# pinky_2_1.net
KiCad netlist of a schematic drawn in EAGLE
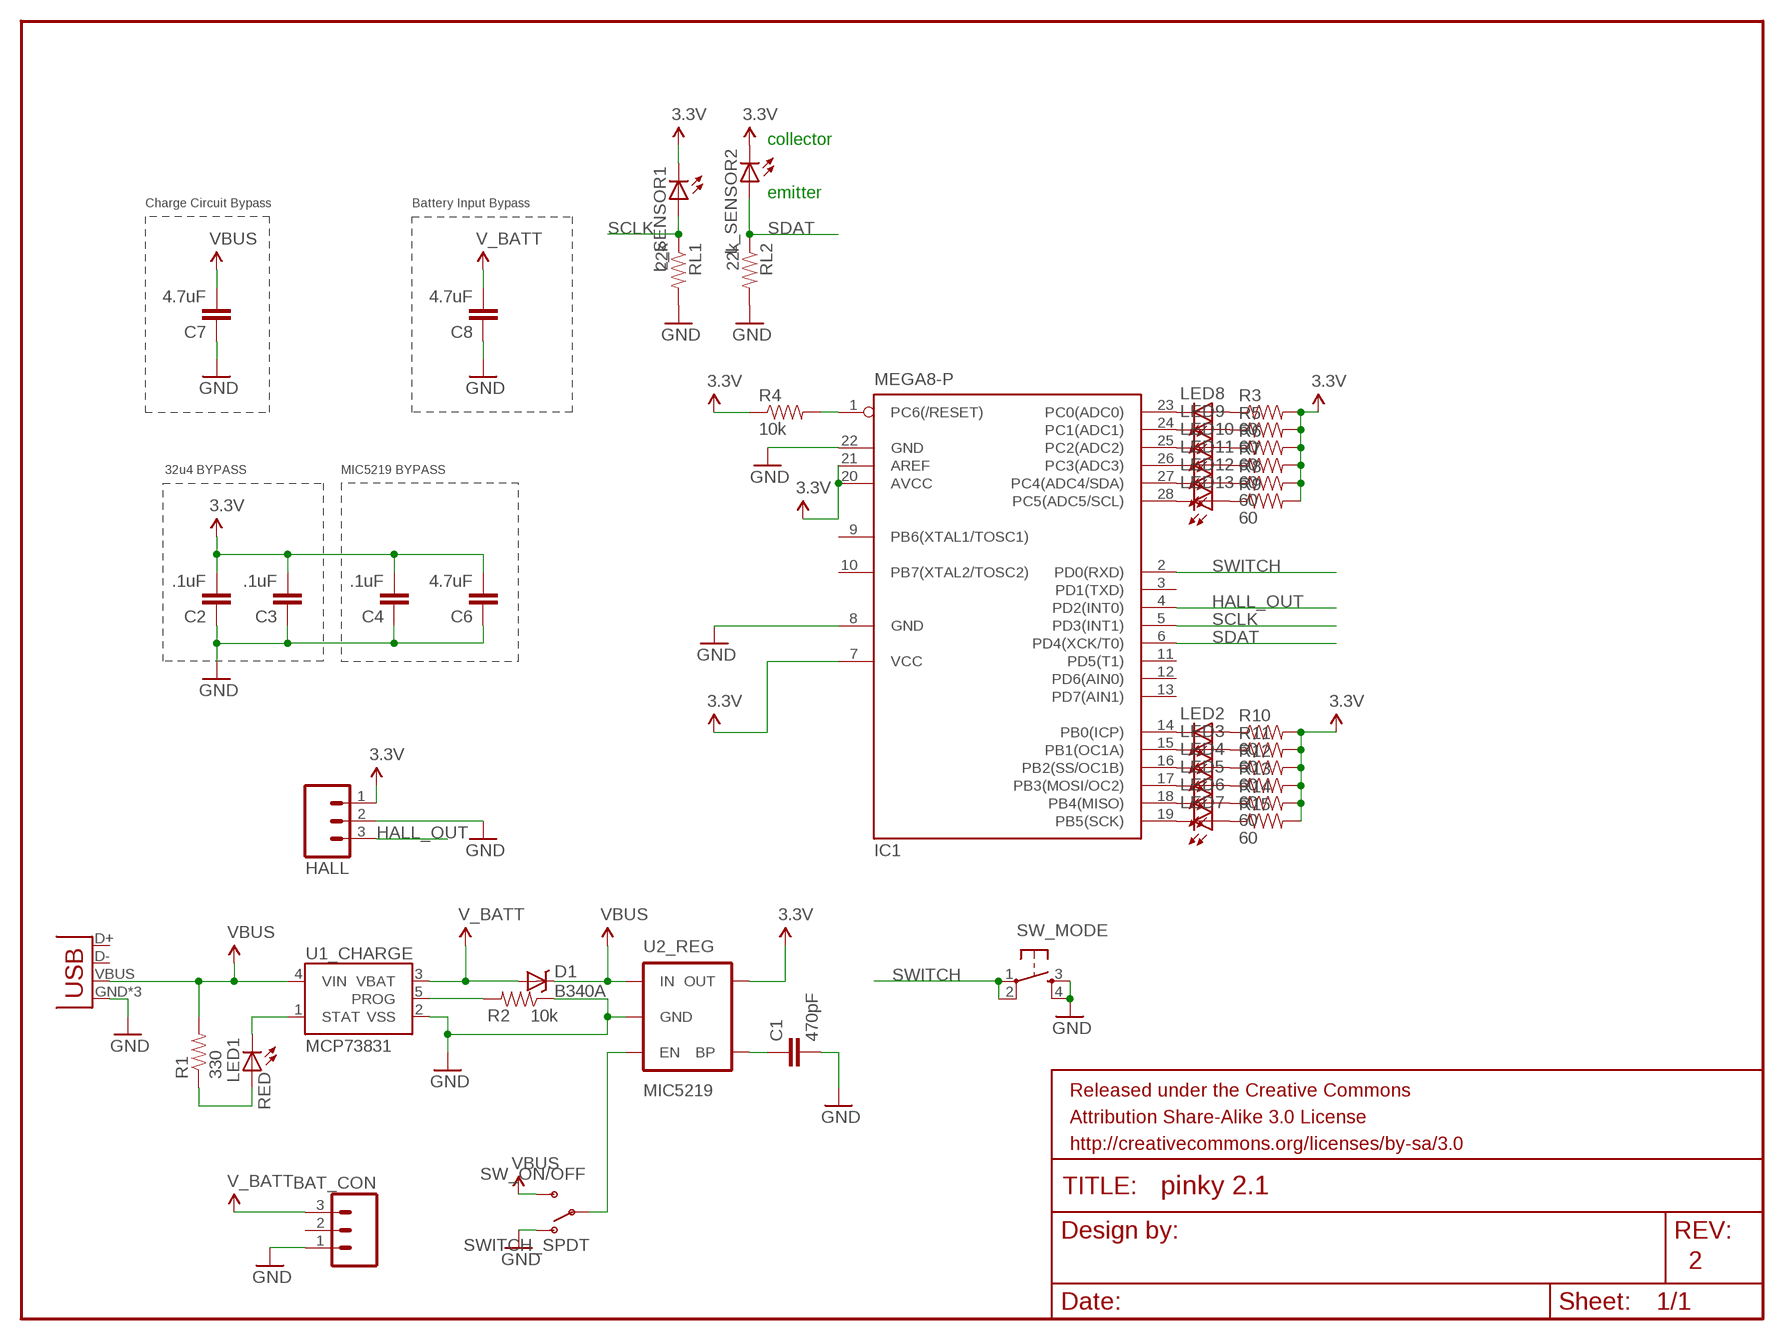
[diagram p0: schematic, sheet 1]

(export (version "E")
  (design (tool "Eeschema 10.0.6"))
  (components
    (comp (ref "BAT_CON")
      (value "M03PTH")
      (footprint "eagle-import:1X03")
      (libsource (lib "eagle-import") (part "M03PTH"))
    )
    (comp (ref "C1")
      (value "470pF")
      (footprint "eagle-import:1206")
      (libsource (lib "eagle-import") (part "CAP1206"))
    )
    (comp (ref "C2")
      (value ".1uF")
      (footprint "eagle-import:1206")
      (libsource (lib "eagle-import") (part "CAP1206"))
    )
    (comp (ref "C3")
      (value ".1uF")
      (footprint "eagle-import:1206")
      (libsource (lib "eagle-import") (part "CAP1206"))
    )
    (comp (ref "C4")
      (value ".1uF")
      (footprint "eagle-import:1206")
      (libsource (lib "eagle-import") (part "CAP1206"))
    )
    (comp (ref "C6")
      (value "4.7uF")
      (footprint "eagle-import:1206")
      (libsource (lib "eagle-import") (part "CAP1206"))
    )
    (comp (ref "C7")
      (value "4.7uF")
      (footprint "eagle-import:1206")
      (libsource (lib "eagle-import") (part "CAP1206"))
    )
    (comp (ref "C8")
      (value "4.7uF")
      (footprint "eagle-import:1206")
      (libsource (lib "eagle-import") (part "CAP1206"))
    )
    (comp (ref "D1")
      (value "B340A")
      (footprint "eagle-import:SMA-DIODE")
      (libsource (lib "eagle-import") (part "DIODE-SCHOTTKY_"))
    )
    (comp (ref "HALL")
      (value "M03PTH")
      (footprint "eagle-import:1X03")
      (libsource (lib "eagle-import") (part "M03PTH"))
    )
    (comp (ref "IC1")
      (value "MEGA8-P")
      (footprint "eagle-import:DIL28-3")
      (libsource (lib "eagle-import") (part "MEGA8-P"))
    )
    (comp (ref "LED1")
      (value "RED")
      (footprint "eagle-import:LED-1206")
      (libsource (lib "eagle-import") (part "LED1206"))
    )
    (comp (ref "LED2")
      (value "LED1206")
      (footprint "eagle-import:LED-1206")
      (libsource (lib "eagle-import") (part "LED1206"))
    )
    (comp (ref "LED3")
      (value "LED1206")
      (footprint "eagle-import:LED-1206")
      (libsource (lib "eagle-import") (part "LED1206"))
    )
    (comp (ref "LED4")
      (value "LED1206")
      (footprint "eagle-import:LED-1206")
      (libsource (lib "eagle-import") (part "LED1206"))
    )
    (comp (ref "LED5")
      (value "LED1206")
      (footprint "eagle-import:LED-1206")
      (libsource (lib "eagle-import") (part "LED1206"))
    )
    (comp (ref "LED6")
      (value "LED1206")
      (footprint "eagle-import:LED-1206")
      (libsource (lib "eagle-import") (part "LED1206"))
    )
    (comp (ref "LED7")
      (value "LED1206")
      (footprint "eagle-import:LED-1206")
      (libsource (lib "eagle-import") (part "LED1206"))
    )
    (comp (ref "LED8")
      (value "LED1206")
      (footprint "eagle-import:LED-1206")
      (libsource (lib "eagle-import") (part "LED1206"))
    )
    (comp (ref "LED9")
      (value "LED1206")
      (footprint "eagle-import:LED-1206")
      (libsource (lib "eagle-import") (part "LED1206"))
    )
    (comp (ref "LED10")
      (value "LED1206")
      (footprint "eagle-import:LED-1206")
      (libsource (lib "eagle-import") (part "LED1206"))
    )
    (comp (ref "LED11")
      (value "LED1206")
      (footprint "eagle-import:LED-1206")
      (libsource (lib "eagle-import") (part "LED1206"))
    )
    (comp (ref "LED12")
      (value "LED1206")
      (footprint "eagle-import:LED-1206")
      (libsource (lib "eagle-import") (part "LED1206"))
    )
    (comp (ref "LED13")
      (value "LED1206")
      (footprint "eagle-import:LED-1206")
      (libsource (lib "eagle-import") (part "LED1206"))
    )
    (comp (ref "L_SENSOR1")
      (value "LED3MM")
      (footprint "eagle-import:LED3MM")
      (libsource (lib "eagle-import") (part "LED3MM"))
    )
    (comp (ref "L_SENSOR2")
      (value "LED3MM")
      (footprint "eagle-import:LED3MM")
      (libsource (lib "eagle-import") (part "LED3MM"))
    )
    (comp (ref "R1")
      (value "330")
      (footprint "eagle-import:1206")
      (libsource (lib "eagle-import") (part "RESISTOR1206"))
    )
    (comp (ref "R2")
      (value "10k")
      (footprint "eagle-import:1206")
      (libsource (lib "eagle-import") (part "RESISTOR1206"))
    )
    (comp (ref "R3")
      (value "60")
      (footprint "eagle-import:1206")
      (libsource (lib "eagle-import") (part "RESISTOR1206"))
    )
    (comp (ref "R4")
      (value "10k")
      (footprint "eagle-import:1206")
      (libsource (lib "eagle-import") (part "RESISTOR1206"))
    )
    (comp (ref "R5")
      (value "60")
      (footprint "eagle-import:1206")
      (libsource (lib "eagle-import") (part "RESISTOR1206"))
    )
    (comp (ref "R6")
      (value "60")
      (footprint "eagle-import:1206")
      (libsource (lib "eagle-import") (part "RESISTOR1206"))
    )
    (comp (ref "R7")
      (value "60")
      (footprint "eagle-import:1206")
      (libsource (lib "eagle-import") (part "RESISTOR1206"))
    )
    (comp (ref "R8")
      (value "60")
      (footprint "eagle-import:1206")
      (libsource (lib "eagle-import") (part "RESISTOR1206"))
    )
    (comp (ref "R9")
      (value "60")
      (footprint "eagle-import:1206")
      (libsource (lib "eagle-import") (part "RESISTOR1206"))
    )
    (comp (ref "R10")
      (value "60")
      (footprint "eagle-import:1206")
      (libsource (lib "eagle-import") (part "RESISTOR1206"))
    )
    (comp (ref "R11")
      (value "60")
      (footprint "eagle-import:1206")
      (libsource (lib "eagle-import") (part "RESISTOR1206"))
    )
    (comp (ref "R12")
      (value "60")
      (footprint "eagle-import:1206")
      (libsource (lib "eagle-import") (part "RESISTOR1206"))
    )
    (comp (ref "R13")
      (value "60")
      (footprint "eagle-import:1206")
      (libsource (lib "eagle-import") (part "RESISTOR1206"))
    )
    (comp (ref "R14")
      (value "60")
      (footprint "eagle-import:1206")
      (libsource (lib "eagle-import") (part "RESISTOR1206"))
    )
    (comp (ref "R15")
      (value "60")
      (footprint "eagle-import:1206")
      (libsource (lib "eagle-import") (part "RESISTOR1206"))
    )
    (comp (ref "RL1")
      (value "22k")
      (footprint "eagle-import:1206")
      (libsource (lib "eagle-import") (part "RESISTOR1206"))
    )
    (comp (ref "RL2")
      (value "22k")
      (footprint "eagle-import:1206")
      (libsource (lib "eagle-import") (part "RESISTOR1206"))
    )
    (comp (ref "SW_MODE")
      (value "TAC_SWITCHPTH")
      (footprint "eagle-import:TACTILE-PTH")
      (libsource (lib "eagle-import") (part "TAC_SWITCHPTH"))
    )
    (comp (ref "SW_ON/OFF")
      (value "SWITCH_SPDT")
      (footprint "eagle-import:KPS-1290")
      (libsource (lib "eagle-import") (part "SWITCH_SPDT"))
    )
    (comp (ref "U1_CHARGE")
      (value "MCP73831")
      (footprint "eagle-import:SOT23-5")
      (libsource (lib "eagle-import") (part "MCP73831"))
    )
    (comp (ref "U2_REG")
      (value "MIC5219")
      (footprint "eagle-import:SOT23-5")
      (libsource (lib "eagle-import") (part "V_REG_MIC5219SMD"))
    )
    (comp (ref "X1_USB_MICRO")
      (value "USB-MICROB")
      (footprint "eagle-import:USB-MICROB")
      (libsource (lib "eagle-import") (part "USB-MICROB"))
    )
  )
  (nets
    (net (code "1") (name "/HALL_OUT") (class "Default")
      (node (ref "HALL") (pin "3") (pinfunction "3_3") (pintype "passive"))
      (node (ref "IC1") (pin "4") (pinfunction "PD2(INT0)_4") (pintype "bidirectional"))
    )
    (net (code "2") (name "/SCLK") (class "Default")
      (node (ref "IC1") (pin "5") (pinfunction "PD3(INT1)_5") (pintype "bidirectional"))
      (node (ref "L_SENSOR1") (pin "A") (pinfunction "A_A") (pintype "passive"))
      (node (ref "RL1") (pin "1") (pinfunction "1_1") (pintype "passive"))
    )
    (net (code "3") (name "/SDAT") (class "Default")
      (node (ref "IC1") (pin "6") (pinfunction "PD4(XCK/T0)_6") (pintype "bidirectional"))
      (node (ref "L_SENSOR2") (pin "A") (pinfunction "A_A") (pintype "passive"))
      (node (ref "RL2") (pin "1") (pinfunction "1_1") (pintype "passive"))
    )
    (net (code "4") (name "/SWITCH") (class "Default")
      (node (ref "IC1") (pin "2") (pinfunction "PD0(RXD)_2") (pintype "bidirectional"))
      (node (ref "SW_MODE") (pin "1") (pinfunction "1_1") (pintype "passive"))
      (node (ref "SW_MODE") (pin "2") (pinfunction "2_2") (pintype "passive"))
    )
    (net (code "5") (name "3.3V") (class "Default")
      (node (ref "C2") (pin "2") (pinfunction "2_2") (pintype "passive"))
      (node (ref "C3") (pin "2") (pinfunction "2_2") (pintype "passive"))
      (node (ref "C4") (pin "2") (pinfunction "2_2") (pintype "passive"))
      (node (ref "C6") (pin "2") (pinfunction "2_2") (pintype "passive"))
      (node (ref "HALL") (pin "1") (pinfunction "1_1") (pintype "passive"))
      (node (ref "IC1") (pin "20") (pinfunction "AVCC_20") (pintype "power_in"))
      (node (ref "IC1") (pin "21") (pinfunction "AREF_21") (pintype "passive"))
      (node (ref "IC1") (pin "7") (pinfunction "VCC_7") (pintype "power_in"))
      (node (ref "L_SENSOR1") (pin "K") (pinfunction "C_K") (pintype "passive"))
      (node (ref "L_SENSOR2") (pin "K") (pinfunction "C_K") (pintype "passive"))
      (node (ref "R10") (pin "2") (pinfunction "2_2") (pintype "passive"))
      (node (ref "R11") (pin "2") (pinfunction "2_2") (pintype "passive"))
      (node (ref "R12") (pin "2") (pinfunction "2_2") (pintype "passive"))
      (node (ref "R13") (pin "2") (pinfunction "2_2") (pintype "passive"))
      (node (ref "R14") (pin "2") (pinfunction "2_2") (pintype "passive"))
      (node (ref "R15") (pin "2") (pinfunction "2_2") (pintype "passive"))
      (node (ref "R3") (pin "2") (pinfunction "2_2") (pintype "passive"))
      (node (ref "R4") (pin "1") (pinfunction "1_1") (pintype "passive"))
      (node (ref "R5") (pin "2") (pinfunction "2_2") (pintype "passive"))
      (node (ref "R6") (pin "2") (pinfunction "2_2") (pintype "passive"))
      (node (ref "R7") (pin "2") (pinfunction "2_2") (pintype "passive"))
      (node (ref "R8") (pin "2") (pinfunction "2_2") (pintype "passive"))
      (node (ref "R9") (pin "2") (pinfunction "2_2") (pintype "passive"))
      (node (ref "U2_REG") (pin "5") (pinfunction "OUT_5") (pintype "passive"))
    )
    (net (code "6") (name "GND") (class "Default")
      (node (ref "BAT_CON") (pin "1") (pinfunction "1_1") (pintype "passive"))
      (node (ref "C1") (pin "2") (pinfunction "2_2") (pintype "passive"))
      (node (ref "C2") (pin "1") (pinfunction "1_1") (pintype "passive"))
      (node (ref "C3") (pin "1") (pinfunction "1_1") (pintype "passive"))
      (node (ref "C4") (pin "1") (pinfunction "1_1") (pintype "passive"))
      (node (ref "C6") (pin "1") (pinfunction "1_1") (pintype "passive"))
      (node (ref "C7") (pin "1") (pinfunction "1_1") (pintype "passive"))
      (node (ref "C8") (pin "1") (pinfunction "1_1") (pintype "passive"))
      (node (ref "HALL") (pin "2") (pinfunction "2_2") (pintype "passive"))
      (node (ref "IC1") (pin "22") (pinfunction "GND_22") (pintype "power_in"))
      (node (ref "IC1") (pin "8") (pinfunction "GND_8") (pintype "power_in"))
      (node (ref "R2") (pin "1") (pinfunction "1_1") (pintype "passive"))
      (node (ref "RL1") (pin "2") (pinfunction "2_2") (pintype "passive"))
      (node (ref "RL2") (pin "2") (pinfunction "2_2") (pintype "passive"))
      (node (ref "SW_MODE") (pin "3") (pinfunction "3_3") (pintype "passive"))
      (node (ref "SW_MODE") (pin "4") (pinfunction "4_4") (pintype "passive"))
      (node (ref "SW_ON/OFF") (pin "O") (pinfunction "O_O") (pintype "passive"))
      (node (ref "U1_CHARGE") (pin "2") (pinfunction "VSS_2") (pintype "power_in"))
      (node (ref "U2_REG") (pin "2") (pinfunction "GND_2") (pintype "input"))
      (node (ref "X1_USB_MICRO") (pin "GND") (pinfunction "GND_GND") (pintype "bidirectional"))
      (node (ref "X1_USB_MICRO") (pin "MT1") (pinfunction "GND_MT1") (pintype "bidirectional"))
      (node (ref "X1_USB_MICRO") (pin "MT2") (pinfunction "GND_MT2") (pintype "bidirectional"))
    )
    (net (code "7") (name "Net-(IC1-PB0(ICP))") (class "Default")
      (node (ref "IC1") (pin "14") (pinfunction "PB0(ICP)_14") (pintype "bidirectional"))
      (node (ref "LED2") (pin "C") (pinfunction "C_C") (pintype "passive"))
    )
    (net (code "8") (name "Net-(IC1-PB1(OC1A))") (class "Default")
      (node (ref "IC1") (pin "15") (pinfunction "PB1(OC1A)_15") (pintype "bidirectional"))
      (node (ref "LED3") (pin "C") (pinfunction "C_C") (pintype "passive"))
    )
    (net (code "9") (name "Net-(IC1-PB2(SS{slash}OC1B))") (class "Default")
      (node (ref "IC1") (pin "16") (pinfunction "PB2(SS/OC1B)_16") (pintype "bidirectional"))
      (node (ref "LED4") (pin "C") (pinfunction "C_C") (pintype "passive"))
    )
    (net (code "10") (name "Net-(IC1-PB3(MOSI{slash}OC2))") (class "Default")
      (node (ref "IC1") (pin "17") (pinfunction "PB3(MOSI/OC2)_17") (pintype "bidirectional"))
      (node (ref "LED5") (pin "C") (pinfunction "C_C") (pintype "passive"))
    )
    (net (code "11") (name "Net-(IC1-PB4(MISO))") (class "Default")
      (node (ref "IC1") (pin "18") (pinfunction "PB4(MISO)_18") (pintype "bidirectional"))
      (node (ref "LED6") (pin "C") (pinfunction "C_C") (pintype "passive"))
    )
    (net (code "12") (name "Net-(IC1-PB5(SCK))") (class "Default")
      (node (ref "IC1") (pin "19") (pinfunction "PB5(SCK)_19") (pintype "bidirectional"))
      (node (ref "LED7") (pin "C") (pinfunction "C_C") (pintype "passive"))
    )
    (net (code "13") (name "Net-(IC1-PC0(ADC0))") (class "Default")
      (node (ref "IC1") (pin "23") (pinfunction "PC0(ADC0)_23") (pintype "bidirectional"))
      (node (ref "LED8") (pin "C") (pinfunction "C_C") (pintype "passive"))
    )
    (net (code "14") (name "Net-(IC1-PC1(ADC1))") (class "Default")
      (node (ref "IC1") (pin "24") (pinfunction "PC1(ADC1)_24") (pintype "bidirectional"))
      (node (ref "LED9") (pin "C") (pinfunction "C_C") (pintype "passive"))
    )
    (net (code "15") (name "Net-(IC1-PC2(ADC2))") (class "Default")
      (node (ref "IC1") (pin "25") (pinfunction "PC2(ADC2)_25") (pintype "bidirectional"))
      (node (ref "LED10") (pin "C") (pinfunction "C_C") (pintype "passive"))
    )
    (net (code "16") (name "Net-(IC1-PC3(ADC3))") (class "Default")
      (node (ref "IC1") (pin "26") (pinfunction "PC3(ADC3)_26") (pintype "bidirectional"))
      (node (ref "LED11") (pin "C") (pinfunction "C_C") (pintype "passive"))
    )
    (net (code "17") (name "Net-(IC1-PC4(ADC4{slash}SDA))") (class "Default")
      (node (ref "IC1") (pin "27") (pinfunction "PC4(ADC4/SDA)_27") (pintype "bidirectional"))
      (node (ref "LED12") (pin "C") (pinfunction "C_C") (pintype "passive"))
    )
    (net (code "18") (name "Net-(IC1-PC5(ADC5{slash}SCL))") (class "Default")
      (node (ref "IC1") (pin "28") (pinfunction "PC5(ADC5/SCL)_28") (pintype "bidirectional"))
      (node (ref "LED13") (pin "C") (pinfunction "C_C") (pintype "passive"))
    )
    (net (code "19") (name "Net-(IC1-PC6({slash}RESET))") (class "Default")
      (node (ref "IC1") (pin "1") (pinfunction "PC6(/RESET)_1") (pintype "bidirectional"))
      (node (ref "R4") (pin "2") (pinfunction "2_2") (pintype "passive"))
    )
    (net (code "20") (name "Net-(LED1-PadA)") (class "Default")
      (node (ref "LED1") (pin "A") (pinfunction "A_A") (pintype "passive"))
      (node (ref "R1") (pin "1") (pinfunction "1_1") (pintype "passive"))
    )
    (net (code "21") (name "Net-(LED2-PadA)") (class "Default")
      (node (ref "LED2") (pin "A") (pinfunction "A_A") (pintype "passive"))
      (node (ref "R10") (pin "1") (pinfunction "1_1") (pintype "passive"))
    )
    (net (code "22") (name "Net-(LED3-PadA)") (class "Default")
      (node (ref "LED3") (pin "A") (pinfunction "A_A") (pintype "passive"))
      (node (ref "R11") (pin "1") (pinfunction "1_1") (pintype "passive"))
    )
    (net (code "23") (name "Net-(LED4-PadA)") (class "Default")
      (node (ref "LED4") (pin "A") (pinfunction "A_A") (pintype "passive"))
      (node (ref "R12") (pin "1") (pinfunction "1_1") (pintype "passive"))
    )
    (net (code "24") (name "Net-(LED5-PadA)") (class "Default")
      (node (ref "LED5") (pin "A") (pinfunction "A_A") (pintype "passive"))
      (node (ref "R13") (pin "1") (pinfunction "1_1") (pintype "passive"))
    )
    (net (code "25") (name "Net-(LED6-PadA)") (class "Default")
      (node (ref "LED6") (pin "A") (pinfunction "A_A") (pintype "passive"))
      (node (ref "R14") (pin "1") (pinfunction "1_1") (pintype "passive"))
    )
    (net (code "26") (name "Net-(LED7-PadA)") (class "Default")
      (node (ref "LED7") (pin "A") (pinfunction "A_A") (pintype "passive"))
      (node (ref "R15") (pin "1") (pinfunction "1_1") (pintype "passive"))
    )
    (net (code "27") (name "Net-(LED8-PadA)") (class "Default")
      (node (ref "LED8") (pin "A") (pinfunction "A_A") (pintype "passive"))
      (node (ref "R3") (pin "1") (pinfunction "1_1") (pintype "passive"))
    )
    (net (code "28") (name "Net-(LED9-PadA)") (class "Default")
      (node (ref "LED9") (pin "A") (pinfunction "A_A") (pintype "passive"))
      (node (ref "R5") (pin "1") (pinfunction "1_1") (pintype "passive"))
    )
    (net (code "29") (name "Net-(LED10-PadA)") (class "Default")
      (node (ref "LED10") (pin "A") (pinfunction "A_A") (pintype "passive"))
      (node (ref "R6") (pin "1") (pinfunction "1_1") (pintype "passive"))
    )
    (net (code "30") (name "Net-(LED11-PadA)") (class "Default")
      (node (ref "LED11") (pin "A") (pinfunction "A_A") (pintype "passive"))
      (node (ref "R7") (pin "1") (pinfunction "1_1") (pintype "passive"))
    )
    (net (code "31") (name "Net-(LED12-PadA)") (class "Default")
      (node (ref "LED12") (pin "A") (pinfunction "A_A") (pintype "passive"))
      (node (ref "R8") (pin "1") (pinfunction "1_1") (pintype "passive"))
    )
    (net (code "32") (name "Net-(LED13-PadA)") (class "Default")
      (node (ref "LED13") (pin "A") (pinfunction "A_A") (pintype "passive"))
      (node (ref "R9") (pin "1") (pinfunction "1_1") (pintype "passive"))
    )
    (net (code "33") (name "Net-(U1_CHARGE-PROG)") (class "Default")
      (node (ref "R2") (pin "2") (pinfunction "2_2") (pintype "passive"))
      (node (ref "U1_CHARGE") (pin "5") (pinfunction "PROG_5") (pintype "input"))
    )
    (net (code "34") (name "Net-(U1_CHARGE-STAT)") (class "Default")
      (node (ref "LED1") (pin "C") (pinfunction "C_C") (pintype "passive"))
      (node (ref "U1_CHARGE") (pin "1") (pinfunction "STAT_1") (pintype "output"))
    )
    (net (code "35") (name "Net-(U2_REG-BP)") (class "Default")
      (node (ref "C1") (pin "1") (pinfunction "1_1") (pintype "passive"))
      (node (ref "U2_REG") (pin "4") (pinfunction "BP_4") (pintype "input"))
    )
    (net (code "36") (name "Net-(U2_REG-EN)") (class "Default")
      (node (ref "SW_ON/OFF") (pin "P") (pinfunction "P_P") (pintype "passive"))
      (node (ref "U2_REG") (pin "3") (pinfunction "EN_3") (pintype "input"))
    )
    (net (code "37") (name "VBUS") (class "Default")
      (node (ref "C7") (pin "2") (pinfunction "2_2") (pintype "passive"))
      (node (ref "D1") (pin "C") (pinfunction "C_C") (pintype "passive"))
      (node (ref "R1") (pin "2") (pinfunction "2_2") (pintype "passive"))
      (node (ref "SW_ON/OFF") (pin "S") (pinfunction "S_S") (pintype "passive"))
      (node (ref "U1_CHARGE") (pin "4") (pinfunction "VIN_4") (pintype "power_in"))
      (node (ref "U2_REG") (pin "1") (pinfunction "IN_1") (pintype "input"))
      (node (ref "X1_USB_MICRO") (pin "VBUS") (pinfunction "VBUS_VBUS") (pintype "bidirectional"))
    )
    (net (code "38") (name "V_BATT") (class "Default")
      (node (ref "BAT_CON") (pin "3") (pinfunction "3_3") (pintype "passive"))
      (node (ref "C8") (pin "2") (pinfunction "2_2") (pintype "passive"))
      (node (ref "D1") (pin "A") (pinfunction "A_A") (pintype "passive"))
      (node (ref "U1_CHARGE") (pin "3") (pinfunction "VBAT_3") (pintype "power_in"))
    )
    (net (code "39") (name "unconnected-(BAT_CON-Pad2)") (class "Default")
      (node (ref "BAT_CON") (pin "2") (pinfunction "2_2") (pintype "passive"))
    )
    (net (code "40") (name "unconnected-(IC1-PB6(XTAL1{slash}TOSC1)-Pad9)") (class "Default")
      (node (ref "IC1") (pin "9") (pinfunction "PB6(XTAL1/TOSC1)_9") (pintype "bidirectional"))
    )
    (net (code "41") (name "unconnected-(IC1-PB7(XTAL2{slash}TOSC2)-Pad10)") (class "Default")
      (node (ref "IC1") (pin "10") (pinfunction "PB7(XTAL2/TOSC2)_10") (pintype "bidirectional"))
    )
    (net (code "42") (name "unconnected-(IC1-PD1(TXD)-Pad3)") (class "Default")
      (node (ref "IC1") (pin "3") (pinfunction "PD1(TXD)_3") (pintype "bidirectional"))
    )
    (net (code "43") (name "unconnected-(IC1-PD5(T1)-Pad11)") (class "Default")
      (node (ref "IC1") (pin "11") (pinfunction "PD5(T1)_11") (pintype "bidirectional"))
    )
    (net (code "44") (name "unconnected-(IC1-PD6(AIN0)-Pad12)") (class "Default")
      (node (ref "IC1") (pin "12") (pinfunction "PD6(AIN0)_12") (pintype "bidirectional"))
    )
    (net (code "45") (name "unconnected-(IC1-PD7(AIN1)-Pad13)") (class "Default")
      (node (ref "IC1") (pin "13") (pinfunction "PD7(AIN1)_13") (pintype "bidirectional"))
    )
    (net (code "46") (name "unconnected-(X1_USB_MICRO-PadD+)") (class "Default")
      (node (ref "X1_USB_MICRO") (pin "D+") (pinfunction "D+_D+") (pintype "bidirectional"))
    )
    (net (code "47") (name "unconnected-(X1_USB_MICRO-PadD-)") (class "Default")
      (node (ref "X1_USB_MICRO") (pin "D-") (pinfunction "D-_D-") (pintype "bidirectional"))
    )
  )
)
